# Pg15_FPGA_5CGX.net
KiCad netlist of a schematic drawn in Altium Designer
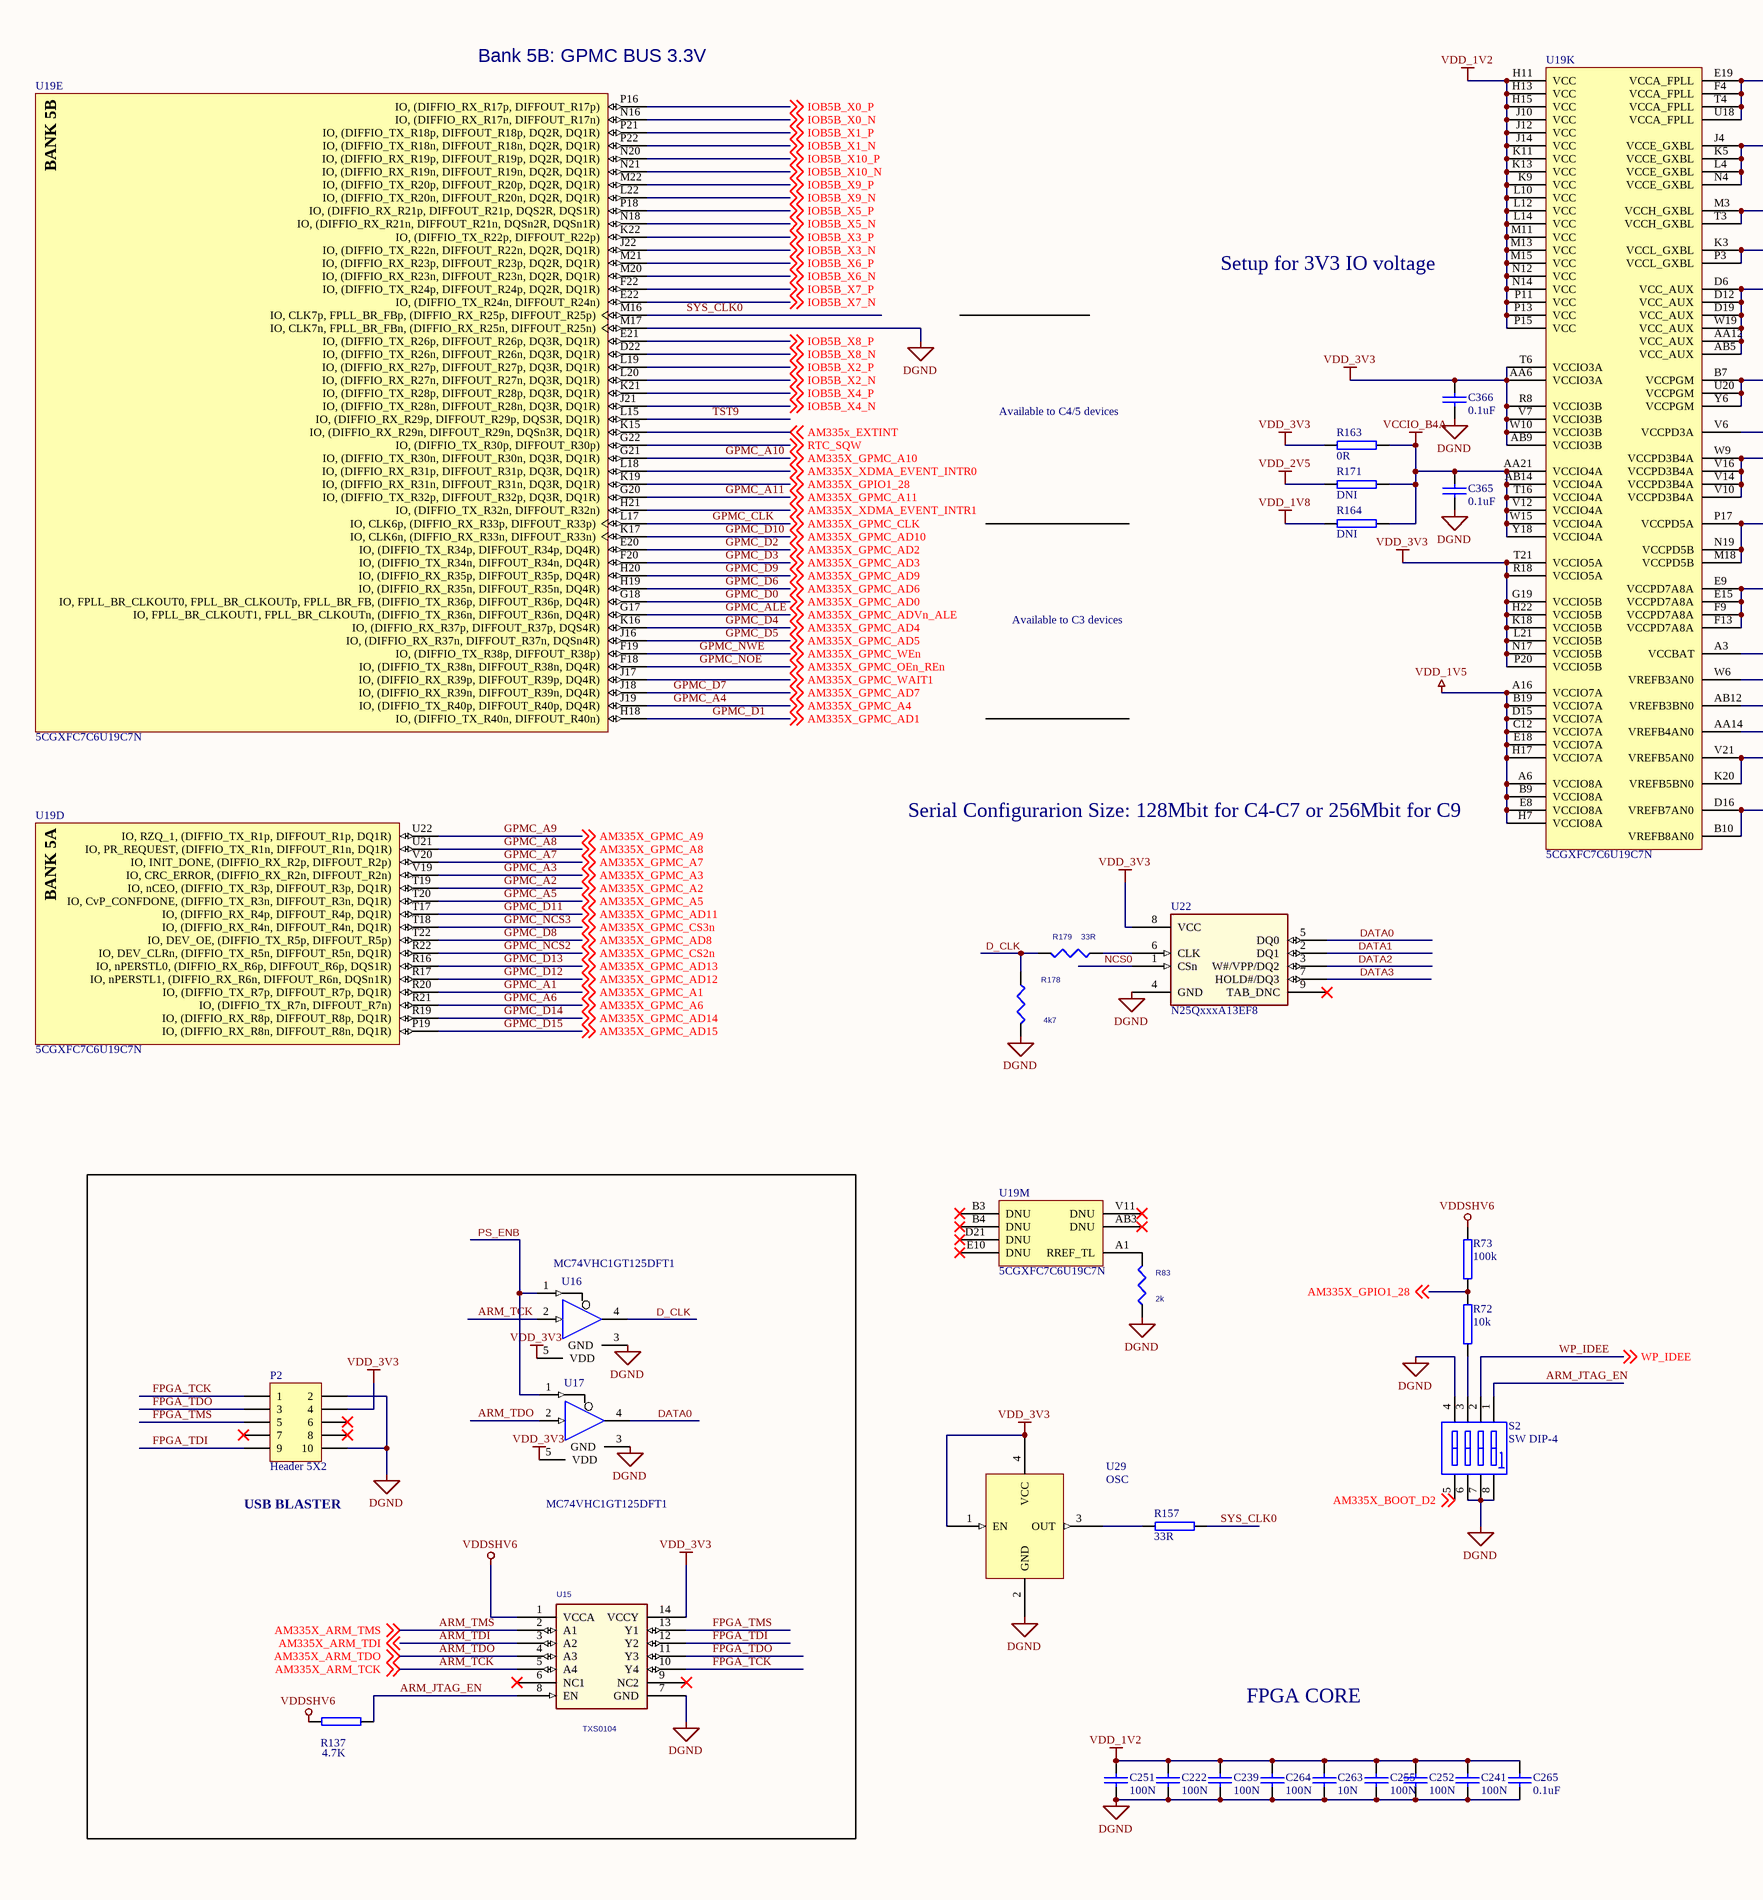
[diagram p0: Pg15_FPGA_5CGX.SchDoc, left]
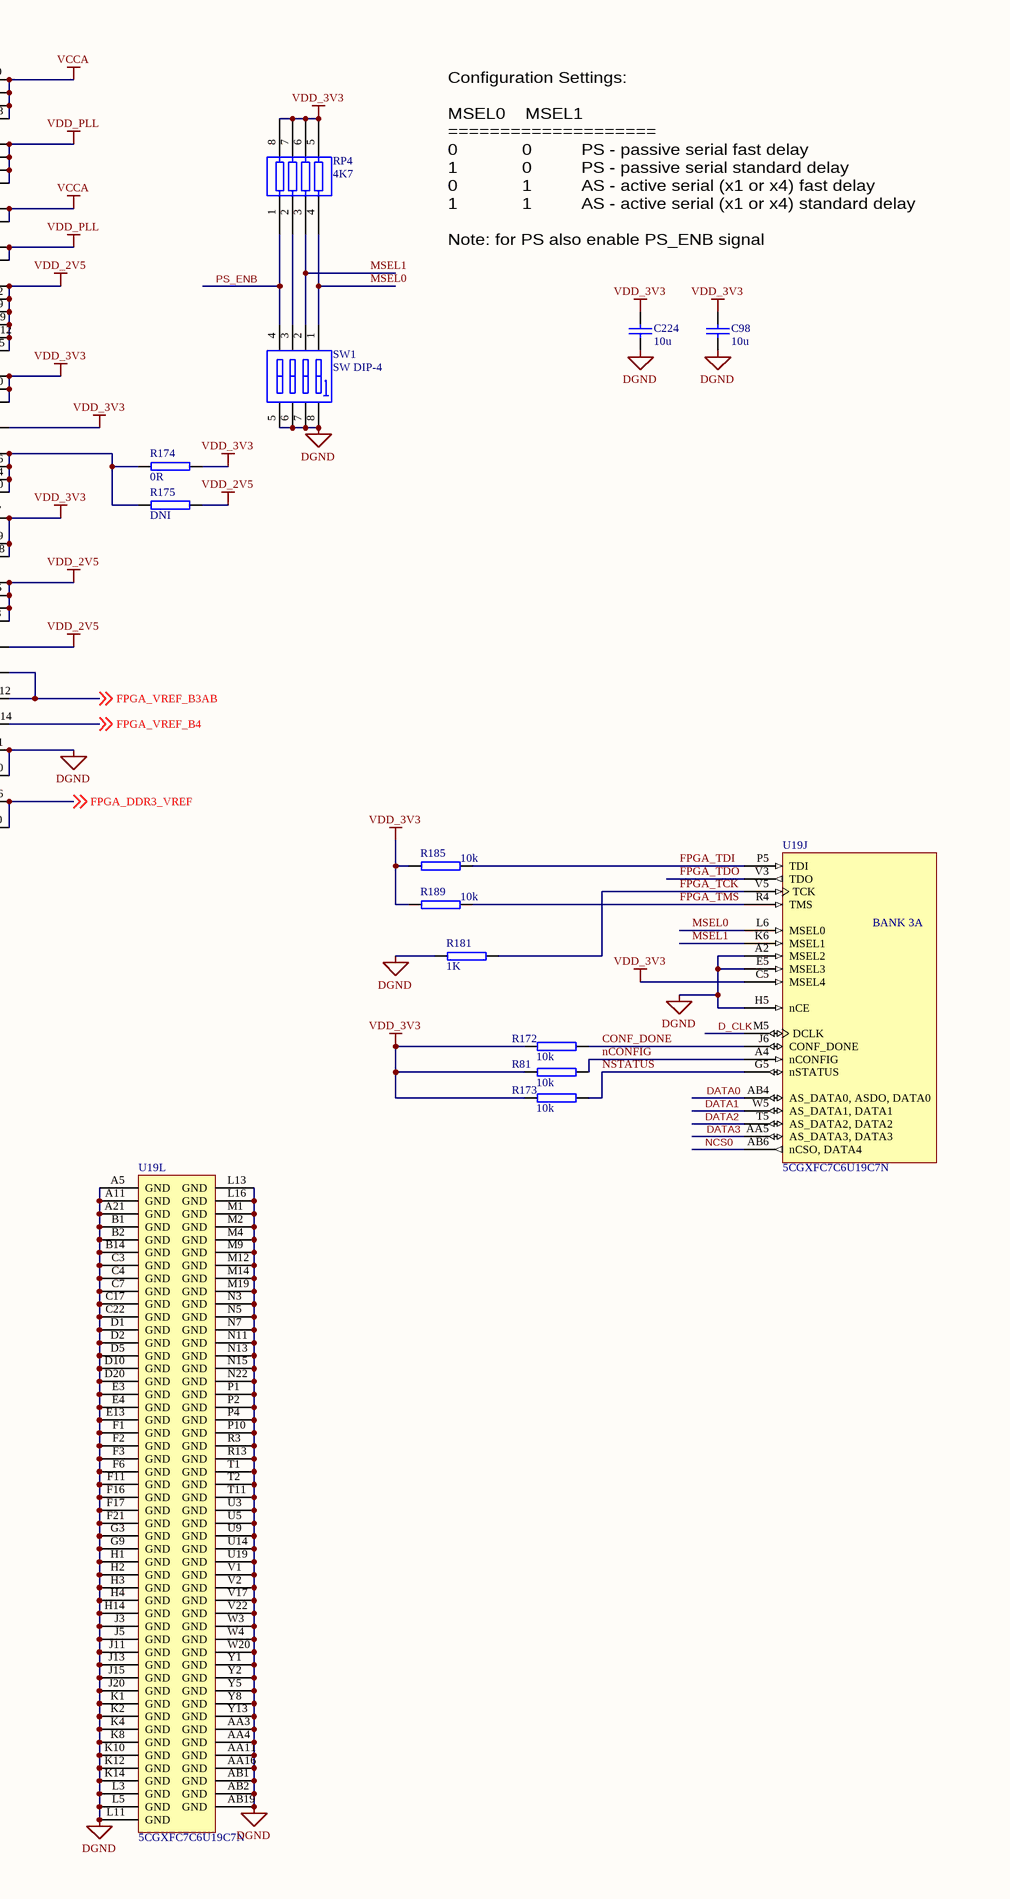
[diagram p1: Pg15_FPGA_5CGX.SchDoc, right]

(export (version "E")
  (design (tool "Eeschema 10.0.6"))
  (components
    (comp (ref "C98")
      (value "10u")
      (footprint "0603")
      (description "NON-POLARISED CAP")
      (libsource (lib "Fireflash_B") (part "CAP"))
    )
    (comp (ref "C222")
      (value "100N")
      (footprint "0603")
      (description "NON-POLARISED CAP")
      (libsource (lib "Fireflash_B") (part "CAP"))
    )
    (comp (ref "C224")
      (value "10u")
      (footprint "0603")
      (description "NON-POLARISED CAP")
      (libsource (lib "Fireflash_B") (part "CAP"))
    )
    (comp (ref "C239")
      (value "100N")
      (footprint "sc0402")
      (description "NON-POLARISED CAP")
      (libsource (lib "Fireflash_B") (part "CAP"))
    )
    (comp (ref "C241")
      (value "100N")
      (footprint "sc0402")
      (description "NON-POLARISED CAP")
      (libsource (lib "Fireflash_B") (part "CAP"))
    )
    (comp (ref "C251")
      (value "100N")
      (footprint "sc0402")
      (description "NON-POLARISED CAP")
      (libsource (lib "Fireflash_B") (part "CAP"))
    )
    (comp (ref "C252")
      (value "100N")
      (footprint "sc0402")
      (description "NON-POLARISED CAP")
      (libsource (lib "Fireflash_B") (part "CAP"))
    )
    (comp (ref "C255")
      (value "100N")
      (footprint "sc0402")
      (description "NON-POLARISED CAP")
      (libsource (lib "Fireflash_B") (part "CAP"))
    )
    (comp (ref "C263")
      (value "10N")
      (footprint "sc0402")
      (description "NON-POLARISED CAP")
      (libsource (lib "Fireflash_B") (part "CAP"))
    )
    (comp (ref "C264")
      (value "100N")
      (footprint "sc0402")
      (description "NON-POLARISED CAP")
      (libsource (lib "Fireflash_B") (part "CAP"))
    )
    (comp (ref "C265")
      (value "0.1uF")
      (footprint "sc0402")
      (description "NON-POLARISED CAP")
      (libsource (lib "Fireflash_B") (part "CAP"))
    )
    (comp (ref "C365")
      (value "0.1uF")
      (footprint "sc0402")
      (description "NON-POLARISED CAP")
      (libsource (lib "Fireflash_B") (part "CAP"))
    )
    (comp (ref "C366")
      (value "0.1uF")
      (footprint "sc0402")
      (description "NON-POLARISED CAP")
      (libsource (lib "Fireflash_B") (part "CAP"))
    )
    (comp (ref "P2")
      (value "Header 5X2")
      (footprint "HDR2X5")
      (description "Header, 5-Pin, Dual row")
      (fields (field (name "PUBLISHER") "Altium Limited"))
      (libsource (lib "Miscellaneous Connectors") (part "Header 5X2"))
    )
    (comp (ref "R72")
      (value "10k")
      (footprint "sc0402")
      (description "Resistor")
      (libsource (lib "Ibis4") (part "RES"))
    )
    (comp (ref "R73")
      (value "100k")
      (footprint "sc0402")
      (description "Resistor")
      (libsource (lib "Ibis4") (part "RES"))
    )
    (comp (ref "R81")
      (value "10k")
      (footprint "sc0402")
      (description "Resistor")
      (libsource (lib "Ibis4") (part "RES"))
    )
    (comp (ref "R83")
      (value "2k")
      (footprint "SM-7351-RES-0402")
      (description "Resistor 10Kohm 1/16W 5% 0402")
      (fields (field (name "MFR") "Rohm") (field (name "TIINTPARTNUMBER") "1R0168"))
      (libsource (lib "*") (part "10KOhmResistor1/16W0402"))
    )
    (comp (ref "R137")
      (value "4.7K")
      (footprint "sc0402")
      (description "RESISTOR")
      (libsource (lib "Fireflash_B") (part "RES"))
    )
    (comp (ref "R157")
      (value "33R")
      (footprint "sc0402")
      (description "Resistor")
      (libsource (lib "Ibis4") (part "RES"))
    )
    (comp (ref "R163")
      (value "0R")
      (footprint "sc0402")
      (description "Resistor")
      (libsource (lib "Ibis4") (part "RES"))
    )
    (comp (ref "R164")
      (value "DNI")
      (footprint "sc0402")
      (description "Resistor")
      (libsource (lib "Ibis4") (part "RES"))
    )
    (comp (ref "R171")
      (value "DNI")
      (footprint "sc0402")
      (description "Resistor")
      (libsource (lib "Ibis4") (part "RES"))
    )
    (comp (ref "R172")
      (value "10k")
      (footprint "sc0402")
      (description "Resistor")
      (libsource (lib "Ibis4") (part "RES"))
    )
    (comp (ref "R173")
      (value "10k")
      (footprint "sc0402")
      (description "Resistor")
      (libsource (lib "Ibis4") (part "RES"))
    )
    (comp (ref "R174")
      (value "0R")
      (footprint "sc0402")
      (description "Resistor")
      (libsource (lib "Ibis4") (part "RES"))
    )
    (comp (ref "R175")
      (value "DNI")
      (footprint "sc0402")
      (description "Resistor")
      (libsource (lib "Ibis4") (part "RES"))
    )
    (comp (ref "R178")
      (value "4k7")
      (footprint "SM-7351-RES-0402")
      (description "Resistor 10Kohm 1/16W 5% 0402")
      (fields (field (name "MFR") "Rohm") (field (name "TIINTPARTNUMBER") "1R0168"))
      (libsource (lib "*") (part "10KOhmResistor1/16W0402"))
    )
    (comp (ref "R179")
      (value "33R")
      (footprint "SM-7351-RES-0402")
      (description "Resistor 10Kohm 1/16W 5% 0402")
      (fields (field (name "MFR") "Rohm") (field (name "TIINTPARTNUMBER") "1R0168"))
      (libsource (lib "*") (part "10KOhmResistor1/16W0402"))
    )
    (comp (ref "R181")
      (value "1K")
      (footprint "sc0402")
      (description "Resistor")
      (libsource (lib "Ibis4") (part "RES"))
    )
    (comp (ref "R185")
      (value "10k")
      (footprint "sc0402")
      (description "Resistor")
      (libsource (lib "Ibis4") (part "RES"))
    )
    (comp (ref "R189")
      (value "10k")
      (footprint "sc0402")
      (description "Resistor")
      (libsource (lib "Ibis4") (part "RES"))
    )
    (comp (ref "RP4")
      (value "4K7")
      (footprint "1206X4")
      (description "QUAD DIP RESISTOR PACK")
      (libsource (lib "*") (part "RESDIP4"))
    )
    (comp (ref "S2")
      (value "SW DIP-4")
      (footprint "PcbLib1:DIPSOP8")
      (description "DIP Switch, 4 Position, SPST")
      (fields (field (name "PUBLISHER") "Altium Limited"))
      (libsource (lib "ARMflash1a") (part "SW DIP-4"))
    )
    (comp (ref "SW1")
      (value "SW DIP-4")
      (footprint "DIPSOP8")
      (description "DIP Switch, 4 Position, SPST")
      (fields (field (name "PUBLISHER") "Altium Limited"))
      (libsource (lib "ARMflashC3_revb") (part "SW DIP-4"))
    )
    (comp (ref "U15")
      (value "TXS0104")
      (footprint "RU-14")
      (description "IC - LOW VOLTAGE 1.2 V TO 5.5 V, 4 CHANNEL, BIDIRECTIONAL, LOGIC LEVEL TRANSLATOR, 14-TSSOP")
      (fields
        (field (name "MANUFACTURER PART NUM") "ADG3304BRUZ")
        (field (name "MANUFACTURER") "Analog Devices")
      )
      (libsource (lib "ARMflash_mini") (part "ADG3304"))
    )
    (comp (ref "U16")
      (value "MC74VHC1GT125DFT1")
      (footprint "419A-01_N")
      (description "Non-Inverting Buffer / CMOS Logic Level Shifter with LSTTL-Compatible Inputs")
      (fields (field (name "PUBLISHER") "Altium Limited"))
      (libsource (lib "ON Semi Logic Buffer Line Driver") (part "MC74VHC1GT125DFT1"))
    )
    (comp (ref "U17")
      (value "MC74VHC1GT125DFT1")
      (footprint "419A-01_N")
      (description "Non-Inverting Buffer / CMOS Logic Level Shifter with LSTTL-Compatible Inputs")
      (fields (field (name "PUBLISHER") "Altium Limited"))
      (libsource (lib "ON Semi Logic Buffer Line Driver") (part "MC74VHC1GT125DFT1"))
    )
    (comp (ref "U19")
      (value "5CGXFC7C6U19C7N")
      (footprint "ALTR-UBGA484_A-190")
      (fields (field (name "MANUFACTURER") "Altera"))
      (libsource (lib "Altera Cyclone V") (part "5CGXFC7C6U19C7N"))
    )
    (comp (ref "U22")
      (value "N25QxxxA13EF8")
      (footprint "QFN127P600X500X85_HS-9N")
      (libsource (lib "C5_SOC_DEVKIT_C_162_Library") (part "N25QxxxA13EF8"))
    )
    (comp (ref "U29")
      (value "OSC")
      (footprint "Osc 3.2x2.5")
      (description "XTAL OSCILLATOR MODULE")
      (libsource (lib "Fireflash_B") (part "OSC"))
    )
  )
  (nets
    (net (code "1") (name "/ARM_JTAG_EN") (class "Default")
      (node (ref "R137") (pin "1") (pintype "passive"))
      (node (ref "S2") (pin "1") (pinfunction "A1_1") (pintype "passive"))
      (node (ref "U15") (pin "8") (pinfunction "EN_8") (pintype "input"))
    )
    (net (code "2") (name "/CONF_DONE") (class "Default")
      (node (ref "R172") (pin "1") (pintype "passive"))
      (node (ref "U19") (pin "J6") (pinfunction "CONF_DONE_J6") (pintype "bidirectional"))
    )
    (net (code "3") (name "/DATA0") (class "Default")
      (node (ref "U17") (pin "4") (pinfunction "Y_4") (pintype "tri_state"))
      (node (ref "U19") (pin "AB4") (pinfunction "AS_DATA0,_ASDO,_DATA0_AB4") (pintype "bidirectional"))
      (node (ref "U22") (pin "5") (pinfunction "DQ0_5") (pintype "bidirectional"))
    )
    (net (code "4") (name "/DATA1") (class "Default")
      (node (ref "U19") (pin "W5") (pinfunction "AS_DATA1,_DATA1_W5") (pintype "bidirectional"))
      (node (ref "U22") (pin "2") (pinfunction "DQ1_2") (pintype "bidirectional"))
    )
    (net (code "5") (name "/DATA2") (class "Default")
      (node (ref "U19") (pin "T5") (pinfunction "AS_DATA2,_DATA2_T5") (pintype "bidirectional"))
      (node (ref "U22") (pin "3") (pinfunction "W#/VPP/DQ2_3") (pintype "bidirectional"))
    )
    (net (code "6") (name "/DATA3") (class "Default")
      (node (ref "U19") (pin "AA5") (pinfunction "AS_DATA3,_DATA3_AA5") (pintype "bidirectional"))
      (node (ref "U22") (pin "7") (pinfunction "HOLD#/DQ3_7") (pintype "bidirectional"))
    )
    (net (code "7") (name "/D_CLK") (class "Default")
      (node (ref "R178") (pin "2") (pinfunction "P2_2") (pintype "passive"))
      (node (ref "R179") (pin "1") (pinfunction "P1_1") (pintype "passive"))
      (node (ref "U16") (pin "4") (pinfunction "Y_4") (pintype "tri_state"))
      (node (ref "U19") (pin "M5") (pinfunction "DCLK_M5") (pintype "bidirectional"))
    )
    (net (code "8") (name "/FPGA_TCK") (class "Default")
      (node (ref "P2") (pin "1") (pinfunction "1_1") (pintype "passive"))
      (node (ref "R181") (pin "1") (pintype "passive"))
      (node (ref "U15") (pin "10") (pinfunction "Y4_10") (pintype "bidirectional"))
      (node (ref "U19") (pin "V5") (pinfunction "TCK_V5") (pintype "input"))
    )
    (net (code "9") (name "/FPGA_TDI") (class "Default")
      (node (ref "P2") (pin "9") (pinfunction "9_9") (pintype "passive"))
      (node (ref "R185") (pin "1") (pintype "passive"))
      (node (ref "U15") (pin "12") (pinfunction "Y2_12") (pintype "bidirectional"))
      (node (ref "U19") (pin "P5") (pinfunction "TDI_P5") (pintype "input"))
    )
    (net (code "10") (name "/FPGA_TDO") (class "Default")
      (node (ref "P2") (pin "3") (pinfunction "3_3") (pintype "passive"))
      (node (ref "U15") (pin "11") (pinfunction "Y3_11") (pintype "bidirectional"))
      (node (ref "U19") (pin "V3") (pinfunction "TDO_V3") (pintype "output"))
    )
    (net (code "11") (name "/FPGA_TMS") (class "Default")
      (node (ref "P2") (pin "5") (pinfunction "5_5") (pintype "passive"))
      (node (ref "R189") (pin "1") (pintype "passive"))
      (node (ref "U15") (pin "13") (pinfunction "Y1_13") (pintype "bidirectional"))
      (node (ref "U19") (pin "R4") (pinfunction "TMS_R4") (pintype "input"))
    )
    (net (code "12") (name "/MSEL0") (class "Default")
      (node (ref "RP4") (pin "4") (pintype "passive"))
      (node (ref "SW1") (pin "1") (pinfunction "A1_1") (pintype "passive"))
      (node (ref "U19") (pin "L6") (pinfunction "MSEL0_L6") (pintype "input"))
    )
    (net (code "13") (name "/MSEL1") (class "Default")
      (node (ref "RP4") (pin "3") (pintype "passive"))
      (node (ref "SW1") (pin "2") (pinfunction "A2_2") (pintype "passive"))
      (node (ref "U19") (pin "K6") (pinfunction "MSEL1_K6") (pintype "input"))
    )
    (net (code "14") (name "/NCS0") (class "Default")
      (node (ref "U19") (pin "AB6") (pinfunction "nCSO,_DATA4_AB6") (pintype "output"))
      (node (ref "U22") (pin "1") (pinfunction "CSn_1") (pintype "input"))
    )
    (net (code "15") (name "/NSTATUS") (class "Default")
      (node (ref "R173") (pin "1") (pintype "passive"))
      (node (ref "U19") (pin "G5") (pinfunction "nSTATUS_G5") (pintype "bidirectional"))
    )
    (net (code "16") (name "/PS_ENB") (class "Default")
      (node (ref "RP4") (pin "1") (pintype "passive"))
      (node (ref "SW1") (pin "4") (pinfunction "A4_4") (pintype "passive"))
      (node (ref "U16") (pin "1") (pinfunction "~{OE}_1") (pintype "input"))
      (node (ref "U17") (pin "1") (pinfunction "~{OE}_1") (pintype "input"))
    )
    (net (code "17") (name "/SYS_CLK0") (class "Default")
      (node (ref "R157") (pin "2") (pintype "passive"))
      (node (ref "U19") (pin "M16") (pinfunction "IO,_CLK7p,_FPLL_BR_FBp,_(DIFFIO_RX_R25p,_DIFFOUT_R25p)_M16") (pintype "bidirectional"))
    )
    (net (code "18") (name "/TST9") (class "Default")
      (node (ref "U19") (pin "L15") (pinfunction "IO,_(DIFFIO_RX_R29p,_DIFFOUT_R29p,_DQS3R,_DQ1R)_L15") (pintype "bidirectional"))
    )
    (net (code "19") (name "/nCONFIG") (class "Default")
      (node (ref "R81") (pin "1") (pintype "passive"))
      (node (ref "U19") (pin "A4") (pinfunction "nCONFIG_A4") (pintype "input"))
    )
    (net (code "20") (name "AM335X_ARM_TCK") (class "Default")
      (node (ref "U15") (pin "5") (pinfunction "A4_5") (pintype "bidirectional"))
      (node (ref "U16") (pin "2") (pinfunction "A_2") (pintype "input"))
    )
    (net (code "21") (name "AM335X_ARM_TDI") (class "Default")
      (node (ref "U15") (pin "3") (pinfunction "A2_3") (pintype "bidirectional"))
    )
    (net (code "22") (name "AM335X_ARM_TDO") (class "Default")
      (node (ref "U15") (pin "4") (pinfunction "A3_4") (pintype "bidirectional"))
      (node (ref "U17") (pin "2") (pinfunction "A_2") (pintype "input"))
    )
    (net (code "23") (name "AM335X_ARM_TMS") (class "Default")
      (node (ref "U15") (pin "2") (pinfunction "A1_2") (pintype "bidirectional"))
    )
    (net (code "24") (name "AM335X_BOOT_D2") (class "Default")
      (node (ref "S2") (pin "5") (pinfunction "B4_5") (pintype "passive"))
    )
    (net (code "25") (name "AM335X_GPIO1_28") (class "Default")
      (node (ref "R72") (pin "2") (pintype "passive"))
      (node (ref "R73") (pin "1") (pintype "passive"))
      (node (ref "U19") (pin "K19") (pinfunction "IO,_(DIFFIO_RX_R31n,_DIFFOUT_R31n,_DQ3R,_DQ1R)_K19") (pintype "bidirectional"))
    )
    (net (code "26") (name "AM335X_GPMC_A1") (class "Default")
      (node (ref "U19") (pin "R20") (pinfunction "IO,_(DIFFIO_TX_R7p,_DIFFOUT_R7p,_DQ1R)_R20") (pintype "bidirectional"))
    )
    (net (code "27") (name "AM335X_GPMC_A2") (class "Default")
      (node (ref "U19") (pin "T19") (pinfunction "IO,_nCEO,_(DIFFIO_TX_R3p,_DIFFOUT_R3p,_DQ1R)_T19") (pintype "bidirectional"))
    )
    (net (code "28") (name "AM335X_GPMC_A3") (class "Default")
      (node (ref "U19") (pin "V19") (pinfunction "IO,_CRC_ERROR,_(DIFFIO_RX_R2n,_DIFFOUT_R2n)_V19") (pintype "bidirectional"))
    )
    (net (code "29") (name "AM335X_GPMC_A4") (class "Default")
      (node (ref "U19") (pin "J19") (pinfunction "IO,_(DIFFIO_TX_R40p,_DIFFOUT_R40p,_DQ4R)_J19") (pintype "bidirectional"))
    )
    (net (code "30") (name "AM335X_GPMC_A5") (class "Default")
      (node (ref "U19") (pin "T20") (pinfunction "IO,_CvP_CONFDONE,_(DIFFIO_TX_R3n,_DIFFOUT_R3n,_DQ1R)_T20") (pintype "bidirectional"))
    )
    (net (code "31") (name "AM335X_GPMC_A6") (class "Default")
      (node (ref "U19") (pin "R21") (pinfunction "IO,_(DIFFIO_TX_R7n,_DIFFOUT_R7n)_R21") (pintype "bidirectional"))
    )
    (net (code "32") (name "AM335X_GPMC_A7") (class "Default")
      (node (ref "U19") (pin "V20") (pinfunction "IO,_INIT_DONE,_(DIFFIO_RX_R2p,_DIFFOUT_R2p)_V20") (pintype "bidirectional"))
    )
    (net (code "33") (name "AM335X_GPMC_A8") (class "Default")
      (node (ref "U19") (pin "U21") (pinfunction "IO,_PR_REQUEST,_(DIFFIO_TX_R1n,_DIFFOUT_R1n,_DQ1R)_U21") (pintype "bidirectional"))
    )
    (net (code "34") (name "AM335X_GPMC_A9") (class "Default")
      (node (ref "U19") (pin "U22") (pinfunction "IO,_RZQ_1,_(DIFFIO_TX_R1p,_DIFFOUT_R1p,_DQ1R)_U22") (pintype "bidirectional"))
    )
    (net (code "35") (name "AM335X_GPMC_A10") (class "Default")
      (node (ref "U19") (pin "G21") (pinfunction "IO,_(DIFFIO_TX_R30n,_DIFFOUT_R30n,_DQ3R,_DQ1R)_G21") (pintype "bidirectional"))
    )
    (net (code "36") (name "AM335X_GPMC_A11") (class "Default")
      (node (ref "U19") (pin "G20") (pinfunction "IO,_(DIFFIO_TX_R32p,_DIFFOUT_R32p,_DQ3R,_DQ1R)_G20") (pintype "bidirectional"))
    )
    (net (code "37") (name "AM335X_GPMC_AD0") (class "Default")
      (node (ref "U19") (pin "G18") (pinfunction "IO,_FPLL_BR_CLKOUT0,_FPLL_BR_CLKOUTp,_FPLL_BR_FB,_(DIFFIO_TX_R36p,_DIFFOUT_R36p,_DQ4R)_G18") (pintype "bidirectional"))
    )
    (net (code "38") (name "AM335X_GPMC_AD1") (class "Default")
      (node (ref "U19") (pin "H18") (pinfunction "IO,_(DIFFIO_TX_R40n,_DIFFOUT_R40n)_H18") (pintype "bidirectional"))
    )
    (net (code "39") (name "AM335X_GPMC_AD2") (class "Default")
      (node (ref "U19") (pin "E20") (pinfunction "IO,_(DIFFIO_TX_R34p,_DIFFOUT_R34p,_DQ4R)_E20") (pintype "bidirectional"))
    )
    (net (code "40") (name "AM335X_GPMC_AD3") (class "Default")
      (node (ref "U19") (pin "F20") (pinfunction "IO,_(DIFFIO_TX_R34n,_DIFFOUT_R34n,_DQ4R)_F20") (pintype "bidirectional"))
    )
    (net (code "41") (name "AM335X_GPMC_AD4") (class "Default")
      (node (ref "U19") (pin "K16") (pinfunction "IO,_(DIFFIO_RX_R37p,_DIFFOUT_R37p,_DQS4R)_K16") (pintype "bidirectional"))
    )
    (net (code "42") (name "AM335X_GPMC_AD5") (class "Default")
      (node (ref "U19") (pin "J16") (pinfunction "IO,_(DIFFIO_RX_R37n,_DIFFOUT_R37n,_DQSn4R)_J16") (pintype "bidirectional"))
    )
    (net (code "43") (name "AM335X_GPMC_AD6") (class "Default")
      (node (ref "U19") (pin "H19") (pinfunction "IO,_(DIFFIO_RX_R35n,_DIFFOUT_R35n,_DQ4R)_H19") (pintype "bidirectional"))
    )
    (net (code "44") (name "AM335X_GPMC_AD7") (class "Default")
      (node (ref "U19") (pin "J18") (pinfunction "IO,_(DIFFIO_RX_R39n,_DIFFOUT_R39n,_DQ4R)_J18") (pintype "bidirectional"))
    )
    (net (code "45") (name "AM335X_GPMC_AD8") (class "Default")
      (node (ref "U19") (pin "T22") (pinfunction "IO,_DEV_OE,_(DIFFIO_TX_R5p,_DIFFOUT_R5p)_T22") (pintype "bidirectional"))
    )
    (net (code "46") (name "AM335X_GPMC_AD9") (class "Default")
      (node (ref "U19") (pin "H20") (pinfunction "IO,_(DIFFIO_RX_R35p,_DIFFOUT_R35p,_DQ4R)_H20") (pintype "bidirectional"))
    )
    (net (code "47") (name "AM335X_GPMC_AD10") (class "Default")
      (node (ref "U19") (pin "K17") (pinfunction "IO,_CLK6n,_(DIFFIO_RX_R33n,_DIFFOUT_R33n)_K17") (pintype "bidirectional"))
    )
    (net (code "48") (name "AM335X_GPMC_AD11") (class "Default")
      (node (ref "U19") (pin "T17") (pinfunction "IO,_(DIFFIO_RX_R4p,_DIFFOUT_R4p,_DQ1R)_T17") (pintype "bidirectional"))
    )
    (net (code "49") (name "AM335X_GPMC_AD12") (class "Default")
      (node (ref "U19") (pin "R17") (pinfunction "IO,_nPERSTL1,_(DIFFIO_RX_R6n,_DIFFOUT_R6n,_DQSn1R)_R17") (pintype "bidirectional"))
    )
    (net (code "50") (name "AM335X_GPMC_AD13") (class "Default")
      (node (ref "U19") (pin "R16") (pinfunction "IO,_nPERSTL0,_(DIFFIO_RX_R6p,_DIFFOUT_R6p,_DQS1R)_R16") (pintype "bidirectional"))
    )
    (net (code "51") (name "AM335X_GPMC_AD14") (class "Default")
      (node (ref "U19") (pin "R19") (pinfunction "IO,_(DIFFIO_RX_R8p,_DIFFOUT_R8p,_DQ1R)_R19") (pintype "bidirectional"))
    )
    (net (code "52") (name "AM335X_GPMC_AD15") (class "Default")
      (node (ref "U19") (pin "P19") (pinfunction "IO,_(DIFFIO_RX_R8n,_DIFFOUT_R8n,_DQ1R)_P19") (pintype "bidirectional"))
    )
    (net (code "53") (name "AM335X_GPMC_ADVn_ALE") (class "Default")
      (node (ref "U19") (pin "G17") (pinfunction "IO,_FPLL_BR_CLKOUT1,_FPLL_BR_CLKOUTn,_(DIFFIO_TX_R36n,_DIFFOUT_R36n,_DQ4R)_G17") (pintype "bidirectional"))
    )
    (net (code "54") (name "AM335X_GPMC_CLK") (class "Default")
      (node (ref "U19") (pin "L17") (pinfunction "IO,_CLK6p,_(DIFFIO_RX_R33p,_DIFFOUT_R33p)_L17") (pintype "bidirectional"))
    )
    (net (code "55") (name "AM335X_GPMC_CS2n") (class "Default")
      (node (ref "U19") (pin "R22") (pinfunction "IO,_DEV_CLRn,_(DIFFIO_TX_R5n,_DIFFOUT_R5n,_DQ1R)_R22") (pintype "bidirectional"))
    )
    (net (code "56") (name "AM335X_GPMC_CS3n") (class "Default")
      (node (ref "U19") (pin "T18") (pinfunction "IO,_(DIFFIO_RX_R4n,_DIFFOUT_R4n,_DQ1R)_T18") (pintype "bidirectional"))
    )
    (net (code "57") (name "AM335X_GPMC_OEn_REn") (class "Default")
      (node (ref "U19") (pin "F18") (pinfunction "IO,_(DIFFIO_TX_R38n,_DIFFOUT_R38n,_DQ4R)_F18") (pintype "bidirectional"))
    )
    (net (code "58") (name "AM335X_GPMC_WAIT1") (class "Default")
      (node (ref "U19") (pin "J17") (pinfunction "IO,_(DIFFIO_RX_R39p,_DIFFOUT_R39p,_DQ4R)_J17") (pintype "bidirectional"))
    )
    (net (code "59") (name "AM335X_GPMC_WEn") (class "Default")
      (node (ref "U19") (pin "F19") (pinfunction "IO,_(DIFFIO_TX_R38p,_DIFFOUT_R38p)_F19") (pintype "bidirectional"))
    )
    (net (code "60") (name "AM335X_XDMA_EVENT_INTR0") (class "Default")
      (node (ref "U19") (pin "L18") (pinfunction "IO,_(DIFFIO_RX_R31p,_DIFFOUT_R31p,_DQ3R,_DQ1R)_L18") (pintype "bidirectional"))
    )
    (net (code "61") (name "AM335X_XDMA_EVENT_INTR1") (class "Default")
      (node (ref "U19") (pin "H21") (pinfunction "IO,_(DIFFIO_TX_R32n,_DIFFOUT_R32n)_H21") (pintype "bidirectional"))
    )
    (net (code "62") (name "AM335x_EXTINT") (class "Default")
      (node (ref "U19") (pin "K15") (pinfunction "IO,_(DIFFIO_RX_R29n,_DIFFOUT_R29n,_DQSn3R,_DQ1R)_K15") (pintype "bidirectional"))
    )
    (net (code "63") (name "DGND") (class "Default")
      (node (ref "C222") (pin "2") (pintype "passive"))
      (node (ref "C224") (pin "2") (pintype "passive"))
      (node (ref "C239") (pin "2") (pintype "passive"))
      (node (ref "C241") (pin "2") (pintype "passive"))
      (node (ref "C251") (pin "2") (pintype "passive"))
      (node (ref "C252") (pin "2") (pintype "passive"))
      (node (ref "C255") (pin "2") (pintype "passive"))
      (node (ref "C263") (pin "2") (pintype "passive"))
      (node (ref "C264") (pin "2") (pintype "passive"))
      (node (ref "C265") (pin "2") (pintype "passive"))
      (node (ref "C365") (pin "2") (pintype "passive"))
      (node (ref "C366") (pin "2") (pintype "passive"))
      (node (ref "C98") (pin "2") (pintype "passive"))
      (node (ref "P2") (pin "10") (pinfunction "10_10") (pintype "passive"))
      (node (ref "P2") (pin "2") (pinfunction "2_2") (pintype "passive"))
      (node (ref "R178") (pin "1") (pinfunction "P1_1") (pintype "passive"))
      (node (ref "R181") (pin "2") (pintype "passive"))
      (node (ref "R83") (pin "2") (pinfunction "P2_2") (pintype "passive"))
      (node (ref "S2") (pin "4") (pinfunction "A4_4") (pintype "passive"))
      (node (ref "S2") (pin "6") (pinfunction "B3_6") (pintype "passive"))
      (node (ref "S2") (pin "7") (pinfunction "B2_7") (pintype "passive"))
      (node (ref "S2") (pin "8") (pinfunction "B1_8") (pintype "passive"))
      (node (ref "SW1") (pin "5") (pinfunction "B4_5") (pintype "passive"))
      (node (ref "SW1") (pin "6") (pinfunction "B3_6") (pintype "passive"))
      (node (ref "SW1") (pin "7") (pinfunction "B2_7") (pintype "passive"))
      (node (ref "SW1") (pin "8") (pinfunction "B1_8") (pintype "passive"))
      (node (ref "U15") (pin "7") (pinfunction "GND_7") (pintype "power_in"))
      (node (ref "U16") (pin "3") (pinfunction "GND_3") (pintype "power_in"))
      (node (ref "U17") (pin "3") (pinfunction "GND_3") (pintype "power_in"))
      (node (ref "U19") (pin "A11") (pinfunction "GND_A11") (pintype "power_in"))
      (node (ref "U19") (pin "A2") (pinfunction "MSEL2_A2") (pintype "input"))
      (node (ref "U19") (pin "A21") (pinfunction "GND_A21") (pintype "power_in"))
      (node (ref "U19") (pin "A5") (pinfunction "GND_A5") (pintype "power_in"))
      (node (ref "U19") (pin "AA11") (pinfunction "GND_AA11") (pintype "power_in"))
      (node (ref "U19") (pin "AA16") (pinfunction "GND_AA16") (pintype "power_in"))
      (node (ref "U19") (pin "AA3") (pinfunction "GND_AA3") (pintype "power_in"))
      (node (ref "U19") (pin "AA4") (pinfunction "GND_AA4") (pintype "power_in"))
      (node (ref "U19") (pin "AB1") (pinfunction "GND_AB1") (pintype "power_in"))
      (node (ref "U19") (pin "AB19") (pinfunction "GND_AB19") (pintype "power_in"))
      (node (ref "U19") (pin "AB2") (pinfunction "GND_AB2") (pintype "power_in"))
      (node (ref "U19") (pin "B1") (pinfunction "GND_B1") (pintype "power_in"))
      (node (ref "U19") (pin "B14") (pinfunction "GND_B14") (pintype "power_in"))
      (node (ref "U19") (pin "B2") (pinfunction "GND_B2") (pintype "power_in"))
      (node (ref "U19") (pin "C17") (pinfunction "GND_C17") (pintype "power_in"))
      (node (ref "U19") (pin "C22") (pinfunction "GND_C22") (pintype "power_in"))
      (node (ref "U19") (pin "C3") (pinfunction "GND_C3") (pintype "power_in"))
      (node (ref "U19") (pin "C4") (pinfunction "GND_C4") (pintype "power_in"))
      (node (ref "U19") (pin "C7") (pinfunction "GND_C7") (pintype "power_in"))
      (node (ref "U19") (pin "D1") (pinfunction "GND_D1") (pintype "power_in"))
      (node (ref "U19") (pin "D10") (pinfunction "GND_D10") (pintype "power_in"))
      (node (ref "U19") (pin "D2") (pinfunction "GND_D2") (pintype "power_in"))
      (node (ref "U19") (pin "D20") (pinfunction "GND_D20") (pintype "power_in"))
      (node (ref "U19") (pin "D5") (pinfunction "GND_D5") (pintype "power_in"))
      (node (ref "U19") (pin "E13") (pinfunction "GND_E13") (pintype "power_in"))
      (node (ref "U19") (pin "E3") (pinfunction "GND_E3") (pintype "power_in"))
      (node (ref "U19") (pin "E4") (pinfunction "GND_E4") (pintype "power_in"))
      (node (ref "U19") (pin "E5") (pinfunction "MSEL3_E5") (pintype "input"))
      (node (ref "U19") (pin "F1") (pinfunction "GND_F1") (pintype "power_in"))
      (node (ref "U19") (pin "F11") (pinfunction "GND_F11") (pintype "power_in"))
      (node (ref "U19") (pin "F16") (pinfunction "GND_F16") (pintype "power_in"))
      (node (ref "U19") (pin "F17") (pinfunction "GND_F17") (pintype "power_in"))
      (node (ref "U19") (pin "F2") (pinfunction "GND_F2") (pintype "power_in"))
      (node (ref "U19") (pin "F21") (pinfunction "GND_F21") (pintype "power_in"))
      (node (ref "U19") (pin "F3") (pinfunction "GND_F3") (pintype "power_in"))
      (node (ref "U19") (pin "F6") (pinfunction "GND_F6") (pintype "power_in"))
      (node (ref "U19") (pin "G3") (pinfunction "GND_G3") (pintype "power_in"))
      (node (ref "U19") (pin "G9") (pinfunction "GND_G9") (pintype "power_in"))
      (node (ref "U19") (pin "H1") (pinfunction "GND_H1") (pintype "power_in"))
      (node (ref "U19") (pin "H14") (pinfunction "GND_H14") (pintype "power_in"))
      (node (ref "U19") (pin "H2") (pinfunction "GND_H2") (pintype "power_in"))
      (node (ref "U19") (pin "H3") (pinfunction "GND_H3") (pintype "power_in"))
      (node (ref "U19") (pin "H4") (pinfunction "GND_H4") (pintype "power_in"))
      (node (ref "U19") (pin "H5") (pinfunction "nCE_H5") (pintype "input"))
      (node (ref "U19") (pin "J11") (pinfunction "GND_J11") (pintype "power_in"))
      (node (ref "U19") (pin "J13") (pinfunction "GND_J13") (pintype "power_in"))
      (node (ref "U19") (pin "J15") (pinfunction "GND_J15") (pintype "power_in"))
      (node (ref "U19") (pin "J20") (pinfunction "GND_J20") (pintype "power_in"))
      (node (ref "U19") (pin "J3") (pinfunction "GND_J3") (pintype "power_in"))
      (node (ref "U19") (pin "J5") (pinfunction "GND_J5") (pintype "power_in"))
      (node (ref "U19") (pin "K1") (pinfunction "GND_K1") (pintype "power_in"))
      (node (ref "U19") (pin "K10") (pinfunction "GND_K10") (pintype "power_in"))
      (node (ref "U19") (pin "K12") (pinfunction "GND_K12") (pintype "power_in"))
      (node (ref "U19") (pin "K14") (pinfunction "GND_K14") (pintype "power_in"))
      (node (ref "U19") (pin "K2") (pinfunction "GND_K2") (pintype "power_in"))
      (node (ref "U19") (pin "K20") (pinfunction "VREFB5BN0_K20") (pintype "power_in"))
      (node (ref "U19") (pin "K4") (pinfunction "GND_K4") (pintype "power_in"))
      (node (ref "U19") (pin "K8") (pinfunction "GND_K8") (pintype "power_in"))
      (node (ref "U19") (pin "L11") (pinfunction "GND_L11") (pintype "power_in"))
      (node (ref "U19") (pin "L13") (pinfunction "GND_L13") (pintype "power_in"))
      (node (ref "U19") (pin "L16") (pinfunction "GND_L16") (pintype "power_in"))
      (node (ref "U19") (pin "L3") (pinfunction "GND_L3") (pintype "power_in"))
      (node (ref "U19") (pin "L5") (pinfunction "GND_L5") (pintype "power_in"))
      (node (ref "U19") (pin "M1") (pinfunction "GND_M1") (pintype "power_in"))
      (node (ref "U19") (pin "M12") (pinfunction "GND_M12") (pintype "power_in"))
      (node (ref "U19") (pin "M14") (pinfunction "GND_M14") (pintype "power_in"))
      (node (ref "U19") (pin "M17") (pinfunction "IO,_CLK7n,_FPLL_BR_FBn,_(DIFFIO_RX_R25n,_DIFFOUT_R25n)_M17") (pintype "bidirectional"))
      (node (ref "U19") (pin "M19") (pinfunction "GND_M19") (pintype "power_in"))
      (node (ref "U19") (pin "M2") (pinfunction "GND_M2") (pintype "power_in"))
      (node (ref "U19") (pin "M4") (pinfunction "GND_M4") (pintype "power_in"))
      (node (ref "U19") (pin "M9") (pinfunction "GND_M9") (pintype "power_in"))
      (node (ref "U19") (pin "N11") (pinfunction "GND_N11") (pintype "power_in"))
      (node (ref "U19") (pin "N13") (pinfunction "GND_N13") (pintype "power_in"))
      (node (ref "U19") (pin "N15") (pinfunction "GND_N15") (pintype "power_in"))
      (node (ref "U19") (pin "N22") (pinfunction "GND_N22") (pintype "power_in"))
      (node (ref "U19") (pin "N3") (pinfunction "GND_N3") (pintype "power_in"))
      (node (ref "U19") (pin "N5") (pinfunction "GND_N5") (pintype "power_in"))
      (node (ref "U19") (pin "N7") (pinfunction "GND_N7") (pintype "power_in"))
      (node (ref "U19") (pin "P1") (pinfunction "GND_P1") (pintype "power_in"))
      (node (ref "U19") (pin "P10") (pinfunction "GND_P10") (pintype "power_in"))
      (node (ref "U19") (pin "P2") (pinfunction "GND_P2") (pintype "power_in"))
      (node (ref "U19") (pin "P4") (pinfunction "GND_P4") (pintype "power_in"))
      (node (ref "U19") (pin "R13") (pinfunction "GND_R13") (pintype "power_in"))
      (node (ref "U19") (pin "R3") (pinfunction "GND_R3") (pintype "power_in"))
      (node (ref "U19") (pin "T1") (pinfunction "GND_T1") (pintype "power_in"))
      (node (ref "U19") (pin "T11") (pinfunction "GND_T11") (pintype "power_in"))
      (node (ref "U19") (pin "T2") (pinfunction "GND_T2") (pintype "power_in"))
      (node (ref "U19") (pin "U14") (pinfunction "GND_U14") (pintype "power_in"))
      (node (ref "U19") (pin "U19") (pinfunction "GND_U19") (pintype "power_in"))
      (node (ref "U19") (pin "U3") (pinfunction "GND_U3") (pintype "power_in"))
      (node (ref "U19") (pin "U5") (pinfunction "GND_U5") (pintype "power_in"))
      (node (ref "U19") (pin "U9") (pinfunction "GND_U9") (pintype "power_in"))
      (node (ref "U19") (pin "V1") (pinfunction "GND_V1") (pintype "power_in"))
      (node (ref "U19") (pin "V17") (pinfunction "GND_V17") (pintype "power_in"))
      (node (ref "U19") (pin "V2") (pinfunction "GND_V2") (pintype "power_in"))
      (node (ref "U19") (pin "V21") (pinfunction "VREFB5AN0_V21") (pintype "power_in"))
      (node (ref "U19") (pin "V22") (pinfunction "GND_V22") (pintype "power_in"))
      (node (ref "U19") (pin "W20") (pinfunction "GND_W20") (pintype "power_in"))
      (node (ref "U19") (pin "W3") (pinfunction "GND_W3") (pintype "power_in"))
      (node (ref "U19") (pin "W4") (pinfunction "GND_W4") (pintype "power_in"))
      (node (ref "U19") (pin "Y1") (pinfunction "GND_Y1") (pintype "power_in"))
      (node (ref "U19") (pin "Y13") (pinfunction "GND_Y13") (pintype "power_in"))
      (node (ref "U19") (pin "Y2") (pinfunction "GND_Y2") (pintype "power_in"))
      (node (ref "U19") (pin "Y5") (pinfunction "GND_Y5") (pintype "power_in"))
      (node (ref "U19") (pin "Y8") (pinfunction "GND_Y8") (pintype "power_in"))
      (node (ref "U22") (pin "4") (pinfunction "GND_4") (pintype "power_in"))
      (node (ref "U29") (pin "2") (pinfunction "GND_2") (pintype "power_in"))
    )
    (net (code "64") (name "FPGA_DDR3_VREF") (class "Default")
      (node (ref "U19") (pin "B10") (pinfunction "VREFB8AN0_B10") (pintype "power_in"))
      (node (ref "U19") (pin "D16") (pinfunction "VREFB7AN0_D16") (pintype "power_in"))
    )
    (net (code "65") (name "FPGA_VREF_B3AB") (class "Default")
      (node (ref "U19") (pin "AB12") (pinfunction "VREFB3BN0_AB12") (pintype "power_in"))
      (node (ref "U19") (pin "W6") (pinfunction "VREFB3AN0_W6") (pintype "power_in"))
    )
    (net (code "66") (name "FPGA_VREF_B4") (class "Default")
      (node (ref "U19") (pin "AA14") (pinfunction "VREFB4AN0_AA14") (pintype "power_in"))
    )
    (net (code "67") (name "IOB5B_X0_N") (class "Default")
      (node (ref "U19") (pin "N16") (pinfunction "IO,_(DIFFIO_RX_R17n,_DIFFOUT_R17n)_N16") (pintype "bidirectional"))
    )
    (net (code "68") (name "IOB5B_X0_P") (class "Default")
      (node (ref "U19") (pin "P16") (pinfunction "IO,_(DIFFIO_RX_R17p,_DIFFOUT_R17p)_P16") (pintype "bidirectional"))
    )
    (net (code "69") (name "IOB5B_X1_N") (class "Default")
      (node (ref "U19") (pin "P22") (pinfunction "IO,_(DIFFIO_TX_R18n,_DIFFOUT_R18n,_DQ2R,_DQ1R)_P22") (pintype "bidirectional"))
    )
    (net (code "70") (name "IOB5B_X1_P") (class "Default")
      (node (ref "U19") (pin "P21") (pinfunction "IO,_(DIFFIO_TX_R18p,_DIFFOUT_R18p,_DQ2R,_DQ1R)_P21") (pintype "bidirectional"))
    )
    (net (code "71") (name "IOB5B_X2_N") (class "Default")
      (node (ref "U19") (pin "L20") (pinfunction "IO,_(DIFFIO_RX_R27n,_DIFFOUT_R27n,_DQ3R,_DQ1R)_L20") (pintype "bidirectional"))
    )
    (net (code "72") (name "IOB5B_X2_P") (class "Default")
      (node (ref "U19") (pin "L19") (pinfunction "IO,_(DIFFIO_RX_R27p,_DIFFOUT_R27p,_DQ3R,_DQ1R)_L19") (pintype "bidirectional"))
    )
    (net (code "73") (name "IOB5B_X3_N") (class "Default")
      (node (ref "U19") (pin "J22") (pinfunction "IO,_(DIFFIO_TX_R22n,_DIFFOUT_R22n,_DQ2R,_DQ1R)_J22") (pintype "bidirectional"))
    )
    (net (code "74") (name "IOB5B_X3_P") (class "Default")
      (node (ref "U19") (pin "K22") (pinfunction "IO,_(DIFFIO_TX_R22p,_DIFFOUT_R22p)_K22") (pintype "bidirectional"))
    )
    (net (code "75") (name "IOB5B_X4_N") (class "Default")
      (node (ref "U19") (pin "J21") (pinfunction "IO,_(DIFFIO_TX_R28n,_DIFFOUT_R28n,_DQ3R,_DQ1R)_J21") (pintype "bidirectional"))
    )
    (net (code "76") (name "IOB5B_X4_P") (class "Default")
      (node (ref "U19") (pin "K21") (pinfunction "IO,_(DIFFIO_TX_R28p,_DIFFOUT_R28p,_DQ3R,_DQ1R)_K21") (pintype "bidirectional"))
    )
    (net (code "77") (name "IOB5B_X5_N") (class "Default")
      (node (ref "U19") (pin "N18") (pinfunction "IO,_(DIFFIO_RX_R21n,_DIFFOUT_R21n,_DQSn2R,_DQSn1R)_N18") (pintype "bidirectional"))
    )
    (net (code "78") (name "IOB5B_X5_P") (class "Default")
      (node (ref "U19") (pin "P18") (pinfunction "IO,_(DIFFIO_RX_R21p,_DIFFOUT_R21p,_DQS2R,_DQS1R)_P18") (pintype "bidirectional"))
    )
    (net (code "79") (name "IOB5B_X6_N") (class "Default")
      (node (ref "U19") (pin "M20") (pinfunction "IO,_(DIFFIO_RX_R23n,_DIFFOUT_R23n,_DQ2R,_DQ1R)_M20") (pintype "bidirectional"))
    )
    (net (code "80") (name "IOB5B_X6_P") (class "Default")
      (node (ref "U19") (pin "M21") (pinfunction "IO,_(DIFFIO_RX_R23p,_DIFFOUT_R23p,_DQ2R,_DQ1R)_M21") (pintype "bidirectional"))
    )
    (net (code "81") (name "IOB5B_X7_N") (class "Default")
      (node (ref "U19") (pin "E22") (pinfunction "IO,_(DIFFIO_TX_R24n,_DIFFOUT_R24n)_E22") (pintype "bidirectional"))
    )
    (net (code "82") (name "IOB5B_X7_P") (class "Default")
      (node (ref "U19") (pin "F22") (pinfunction "IO,_(DIFFIO_TX_R24p,_DIFFOUT_R24p,_DQ2R,_DQ1R)_F22") (pintype "bidirectional"))
    )
    (net (code "83") (name "IOB5B_X8_N") (class "Default")
      (node (ref "U19") (pin "D22") (pinfunction "IO,_(DIFFIO_TX_R26n,_DIFFOUT_R26n,_DQ3R,_DQ1R)_D22") (pintype "bidirectional"))
    )
    (net (code "84") (name "IOB5B_X8_P") (class "Default")
      (node (ref "U19") (pin "E21") (pinfunction "IO,_(DIFFIO_TX_R26p,_DIFFOUT_R26p,_DQ3R,_DQ1R)_E21") (pintype "bidirectional"))
    )
    (net (code "85") (name "IOB5B_X9_N") (class "Default")
      (node (ref "U19") (pin "L22") (pinfunction "IO,_(DIFFIO_TX_R20n,_DIFFOUT_R20n,_DQ2R,_DQ1R)_L22") (pintype "bidirectional"))
    )
    (net (code "86") (name "IOB5B_X9_P") (class "Default")
      (node (ref "U19") (pin "M22") (pinfunction "IO,_(DIFFIO_TX_R20p,_DIFFOUT_R20p,_DQ2R,_DQ1R)_M22") (pintype "bidirectional"))
    )
    (net (code "87") (name "IOB5B_X10_N") (class "Default")
      (node (ref "U19") (pin "N21") (pinfunction "IO,_(DIFFIO_RX_R19n,_DIFFOUT_R19n,_DQ2R,_DQ1R)_N21") (pintype "bidirectional"))
    )
    (net (code "88") (name "IOB5B_X10_P") (class "Default")
      (node (ref "U19") (pin "N20") (pinfunction "IO,_(DIFFIO_RX_R19p,_DIFFOUT_R19p,_DQ2R,_DQ1R)_N20") (pintype "bidirectional"))
    )
    (net (code "89") (name "Net-(R83-P1)") (class "Default")
      (node (ref "R83") (pin "1") (pinfunction "P1_1") (pintype "passive"))
      (node (ref "U19") (pin "A1") (pinfunction "RREF_TL_A1") (pintype "passive"))
    )
    (net (code "90") (name "Net-(R174-Pad2)") (class "Default")
      (node (ref "R174") (pin "2") (pintype "passive"))
      (node (ref "R175") (pin "2") (pintype "passive"))
      (node (ref "U19") (pin "V10") (pinfunction "VCCPD3B4A_V10") (pintype "power_in"))
      (node (ref "U19") (pin "V14") (pinfunction "VCCPD3B4A_V14") (pintype "power_in"))
      (node (ref "U19") (pin "V16") (pinfunction "VCCPD3B4A_V16") (pintype "power_in"))
      (node (ref "U19") (pin "W9") (pinfunction "VCCPD3B4A_W9") (pintype "power_in"))
    )
    (net (code "91") (name "Net-(R179-P2)") (class "Default")
      (node (ref "R179") (pin "2") (pinfunction "P2_2") (pintype "passive"))
      (node (ref "U22") (pin "6") (pinfunction "CLK_6") (pintype "input"))
    )
    (net (code "92") (name "Net-(S2-A3)") (class "Default")
      (node (ref "R72") (pin "1") (pintype "passive"))
      (node (ref "S2") (pin "3") (pinfunction "A3_3") (pintype "passive"))
    )
    (net (code "93") (name "Net-(SW1-A3)") (class "Default")
      (node (ref "RP4") (pin "2") (pintype "passive"))
      (node (ref "SW1") (pin "3") (pinfunction "A3_3") (pintype "passive"))
    )
    (net (code "94") (name "Net-(U29-OUT)") (class "Default")
      (node (ref "R157") (pin "1") (pintype "passive"))
      (node (ref "U29") (pin "3") (pinfunction "OUT_3") (pintype "output"))
    )
    (net (code "95") (name "RTC_SQW") (class "Default")
      (node (ref "U19") (pin "G22") (pinfunction "IO,_(DIFFIO_TX_R30p,_DIFFOUT_R30p)_G22") (pintype "bidirectional"))
    )
    (net (code "96") (name "VCCA") (class "Default")
      (node (ref "U19") (pin "E19") (pinfunction "VCCA_FPLL_E19") (pintype "power_in"))
      (node (ref "U19") (pin "F4") (pinfunction "VCCA_FPLL_F4") (pintype "power_in"))
      (node (ref "U19") (pin "M3") (pinfunction "VCCH_GXBL_M3") (pintype "power_in"))
      (node (ref "U19") (pin "T3") (pinfunction "VCCH_GXBL_T3") (pintype "power_in"))
      (node (ref "U19") (pin "T4") (pinfunction "VCCA_FPLL_T4") (pintype "power_in"))
      (node (ref "U19") (pin "U18") (pinfunction "VCCA_FPLL_U18") (pintype "power_in"))
    )
    (net (code "97") (name "VCCIO_B4A") (class "Default")
      (node (ref "C365") (pin "1") (pintype "passive"))
      (node (ref "R163") (pin "1") (pintype "passive"))
      (node (ref "R164") (pin "1") (pintype "passive"))
      (node (ref "R171") (pin "1") (pintype "passive"))
      (node (ref "U19") (pin "AA21") (pinfunction "VCCIO4A_AA21") (pintype "power_in"))
      (node (ref "U19") (pin "AB14") (pinfunction "VCCIO4A_AB14") (pintype "power_in"))
      (node (ref "U19") (pin "T16") (pinfunction "VCCIO4A_T16") (pintype "power_in"))
      (node (ref "U19") (pin "V12") (pinfunction "VCCIO4A_V12") (pintype "power_in"))
      (node (ref "U19") (pin "W15") (pinfunction "VCCIO4A_W15") (pintype "power_in"))
      (node (ref "U19") (pin "Y18") (pinfunction "VCCIO4A_Y18") (pintype "power_in"))
    )
    (net (code "98") (name "VDDSHV6") (class "Default")
      (node (ref "R137") (pin "2") (pintype "passive"))
      (node (ref "R73") (pin "2") (pintype "passive"))
      (node (ref "U15") (pin "1") (pinfunction "VCCA_1") (pintype "power_in"))
    )
    (net (code "99") (name "VDD_1V2") (class "Default")
      (node (ref "C222") (pin "1") (pintype "passive"))
      (node (ref "C239") (pin "1") (pintype "passive"))
      (node (ref "C241") (pin "1") (pintype "passive"))
      (node (ref "C251") (pin "1") (pintype "passive"))
      (node (ref "C252") (pin "1") (pintype "passive"))
      (node (ref "C255") (pin "1") (pintype "passive"))
      (node (ref "C263") (pin "1") (pintype "passive"))
      (node (ref "C264") (pin "1") (pintype "passive"))
      (node (ref "C265") (pin "1") (pintype "passive"))
      (node (ref "U19") (pin "H11") (pinfunction "VCC_H11") (pintype "power_in"))
      (node (ref "U19") (pin "H13") (pinfunction "VCC_H13") (pintype "power_in"))
      (node (ref "U19") (pin "H15") (pinfunction "VCC_H15") (pintype "power_in"))
      (node (ref "U19") (pin "J10") (pinfunction "VCC_J10") (pintype "power_in"))
      (node (ref "U19") (pin "J12") (pinfunction "VCC_J12") (pintype "power_in"))
      (node (ref "U19") (pin "J14") (pinfunction "VCC_J14") (pintype "power_in"))
      (node (ref "U19") (pin "K11") (pinfunction "VCC_K11") (pintype "power_in"))
      (node (ref "U19") (pin "K13") (pinfunction "VCC_K13") (pintype "power_in"))
      (node (ref "U19") (pin "K9") (pinfunction "VCC_K9") (pintype "power_in"))
      (node (ref "U19") (pin "L10") (pinfunction "VCC_L10") (pintype "power_in"))
      (node (ref "U19") (pin "L12") (pinfunction "VCC_L12") (pintype "power_in"))
      (node (ref "U19") (pin "L14") (pinfunction "VCC_L14") (pintype "power_in"))
      (node (ref "U19") (pin "M11") (pinfunction "VCC_M11") (pintype "power_in"))
      (node (ref "U19") (pin "M13") (pinfunction "VCC_M13") (pintype "power_in"))
      (node (ref "U19") (pin "M15") (pinfunction "VCC_M15") (pintype "power_in"))
      (node (ref "U19") (pin "N12") (pinfunction "VCC_N12") (pintype "power_in"))
      (node (ref "U19") (pin "N14") (pinfunction "VCC_N14") (pintype "power_in"))
      (node (ref "U19") (pin "P11") (pinfunction "VCC_P11") (pintype "power_in"))
      (node (ref "U19") (pin "P13") (pinfunction "VCC_P13") (pintype "power_in"))
      (node (ref "U19") (pin "P15") (pinfunction "VCC_P15") (pintype "power_in"))
    )
    (net (code "100") (name "VDD_1V5") (class "Default")
      (node (ref "U19") (pin "A16") (pinfunction "VCCIO7A_A16") (pintype "power_in"))
      (node (ref "U19") (pin "A6") (pinfunction "VCCIO8A_A6") (pintype "power_in"))
      (node (ref "U19") (pin "B19") (pinfunction "VCCIO7A_B19") (pintype "power_in"))
      (node (ref "U19") (pin "B9") (pinfunction "VCCIO8A_B9") (pintype "power_in"))
      (node (ref "U19") (pin "C12") (pinfunction "VCCIO7A_C12") (pintype "power_in"))
      (node (ref "U19") (pin "D15") (pinfunction "VCCIO7A_D15") (pintype "power_in"))
      (node (ref "U19") (pin "E18") (pinfunction "VCCIO7A_E18") (pintype "power_in"))
      (node (ref "U19") (pin "E8") (pinfunction "VCCIO8A_E8") (pintype "power_in"))
      (node (ref "U19") (pin "H17") (pinfunction "VCCIO7A_H17") (pintype "power_in"))
      (node (ref "U19") (pin "H7") (pinfunction "VCCIO8A_H7") (pintype "power_in"))
    )
    (net (code "101") (name "VDD_1V8") (class "Default") (node (ref "R164") (pin "2") (pintype "passive")))
    (net (code "102") (name "VDD_2V5") (class "Default")
      (node (ref "R171") (pin "2") (pintype "passive"))
      (node (ref "R175") (pin "1") (pintype "passive"))
      (node (ref "U19") (pin "A3") (pinfunction "VCCBAT_A3") (pintype "power_in"))
      (node (ref "U19") (pin "AA12") (pinfunction "VCC_AUX_AA12") (pintype "power_in"))
      (node (ref "U19") (pin "AB5") (pinfunction "VCC_AUX_AB5") (pintype "power_in"))
      (node (ref "U19") (pin "D12") (pinfunction "VCC_AUX_D12") (pintype "power_in"))
      (node (ref "U19") (pin "D19") (pinfunction "VCC_AUX_D19") (pintype "power_in"))
      (node (ref "U19") (pin "D6") (pinfunction "VCC_AUX_D6") (pintype "power_in"))
      (node (ref "U19") (pin "E15") (pinfunction "VCCPD7A8A_E15") (pintype "power_in"))
      (node (ref "U19") (pin "E9") (pinfunction "VCCPD7A8A_E9") (pintype "power_in"))
      (node (ref "U19") (pin "F13") (pinfunction "VCCPD7A8A_F13") (pintype "power_in"))
      (node (ref "U19") (pin "F9") (pinfunction "VCCPD7A8A_F9") (pintype "power_in"))
      (node (ref "U19") (pin "W19") (pinfunction "VCC_AUX_W19") (pintype "power_in"))
    )
    (net (code "103") (name "VDD_3V3") (class "Default")
      (node (ref "C224") (pin "1") (pintype "passive"))
      (node (ref "C366") (pin "1") (pintype "passive"))
      (node (ref "C98") (pin "1") (pintype "passive"))
      (node (ref "P2") (pin "4") (pinfunction "4_4") (pintype "passive"))
      (node (ref "R163") (pin "2") (pintype "passive"))
      (node (ref "R172") (pin "2") (pintype "passive"))
      (node (ref "R173") (pin "2") (pintype "passive"))
      (node (ref "R174") (pin "1") (pintype "passive"))
      (node (ref "R185") (pin "2") (pintype "passive"))
      (node (ref "R189") (pin "2") (pintype "passive"))
      (node (ref "R81") (pin "2") (pintype "passive"))
      (node (ref "RP4") (pin "5") (pintype "passive"))
      (node (ref "RP4") (pin "6") (pintype "passive"))
      (node (ref "RP4") (pin "7") (pintype "passive"))
      (node (ref "RP4") (pin "8") (pintype "passive"))
      (node (ref "U15") (pin "14") (pinfunction "VCCY_14") (pintype "power_in"))
      (node (ref "U16") (pin "5") (pinfunction "VDD_5") (pintype "power_in"))
      (node (ref "U17") (pin "5") (pinfunction "VDD_5") (pintype "power_in"))
      (node (ref "U19") (pin "AA6") (pinfunction "VCCIO3A_AA6") (pintype "power_in"))
      (node (ref "U19") (pin "AB9") (pinfunction "VCCIO3B_AB9") (pintype "power_in"))
      (node (ref "U19") (pin "B7") (pinfunction "VCCPGM_B7") (pintype "power_in"))
      (node (ref "U19") (pin "C5") (pinfunction "MSEL4_C5") (pintype "input"))
      (node (ref "U19") (pin "G19") (pinfunction "VCCIO5B_G19") (pintype "power_in"))
      (node (ref "U19") (pin "H22") (pinfunction "VCCIO5B_H22") (pintype "power_in"))
      (node (ref "U19") (pin "K18") (pinfunction "VCCIO5B_K18") (pintype "power_in"))
      (node (ref "U19") (pin "L21") (pinfunction "VCCIO5B_L21") (pintype "power_in"))
      (node (ref "U19") (pin "M18") (pinfunction "VCCPD5B_M18") (pintype "power_in"))
      (node (ref "U19") (pin "N17") (pinfunction "VCCIO5B_N17") (pintype "power_in"))
      (node (ref "U19") (pin "N19") (pinfunction "VCCPD5B_N19") (pintype "power_in"))
      (node (ref "U19") (pin "P17") (pinfunction "VCCPD5A_P17") (pintype "power_in"))
      (node (ref "U19") (pin "P20") (pinfunction "VCCIO5B_P20") (pintype "power_in"))
      (node (ref "U19") (pin "R18") (pinfunction "VCCIO5A_R18") (pintype "power_in"))
      (node (ref "U19") (pin "R8") (pinfunction "VCCIO3B_R8") (pintype "power_in"))
      (node (ref "U19") (pin "T21") (pinfunction "VCCIO5A_T21") (pintype "power_in"))
      (node (ref "U19") (pin "T6") (pinfunction "VCCIO3A_T6") (pintype "power_in"))
      (node (ref "U19") (pin "U20") (pinfunction "VCCPGM_U20") (pintype "power_in"))
      (node (ref "U19") (pin "V6") (pinfunction "VCCPD3A_V6") (pintype "power_in"))
      (node (ref "U19") (pin "V7") (pinfunction "VCCIO3B_V7") (pintype "power_in"))
      (node (ref "U19") (pin "W10") (pinfunction "VCCIO3B_W10") (pintype "power_in"))
      (node (ref "U19") (pin "Y6") (pinfunction "VCCPGM_Y6") (pintype "power_in"))
      (node (ref "U22") (pin "8") (pinfunction "VCC_8") (pintype "power_in"))
      (node (ref "U29") (pin "1") (pinfunction "EN_1") (pintype "input"))
      (node (ref "U29") (pin "4") (pinfunction "VCC_4") (pintype "power_in"))
    )
    (net (code "104") (name "VDD_PLL") (class "Default")
      (node (ref "U19") (pin "J4") (pinfunction "VCCE_GXBL_J4") (pintype "power_in"))
      (node (ref "U19") (pin "K3") (pinfunction "VCCL_GXBL_K3") (pintype "power_in"))
      (node (ref "U19") (pin "K5") (pinfunction "VCCE_GXBL_K5") (pintype "power_in"))
      (node (ref "U19") (pin "L4") (pinfunction "VCCE_GXBL_L4") (pintype "power_in"))
      (node (ref "U19") (pin "N4") (pinfunction "VCCE_GXBL_N4") (pintype "power_in"))
      (node (ref "U19") (pin "P3") (pinfunction "VCCL_GXBL_P3") (pintype "power_in"))
    )
    (net (code "105") (name "WP_IDEE") (class "Default")
      (node (ref "S2") (pin "2") (pinfunction "A2_2") (pintype "passive"))
    )
    (net (code "106") (name "unconnected-(P2-Pad6)") (class "Default")
      (node (ref "P2") (pin "6") (pinfunction "6_6") (pintype "passive+no_connect"))
    )
    (net (code "107") (name "unconnected-(P2-Pad7)") (class "Default")
      (node (ref "P2") (pin "7") (pinfunction "7_7") (pintype "passive+no_connect"))
    )
    (net (code "108") (name "unconnected-(P2-Pad8)") (class "Default")
      (node (ref "P2") (pin "8") (pinfunction "8_8") (pintype "passive+no_connect"))
    )
    (net (code "109") (name "unconnected-(U15-NC1-Pad6)") (class "Default")
      (node (ref "U15") (pin "6") (pinfunction "NC1_6") (pintype "passive+no_connect"))
    )
    (net (code "110") (name "unconnected-(U15-NC2-Pad9)") (class "Default")
      (node (ref "U15") (pin "9") (pinfunction "NC2_9") (pintype "passive+no_connect"))
    )
    (net (code "111") (name "unconnected-(U19M-DNU-PadAB3)") (class "Default")
      (node (ref "U19") (pin "AB3") (pinfunction "DNU_AB3") (pintype "passive+no_connect"))
    )
    (net (code "112") (name "unconnected-(U19M-DNU-PadB3)") (class "Default")
      (node (ref "U19") (pin "B3") (pinfunction "DNU_B3") (pintype "passive+no_connect"))
    )
    (net (code "113") (name "unconnected-(U19M-DNU-PadB4)") (class "Default")
      (node (ref "U19") (pin "B4") (pinfunction "DNU_B4") (pintype "passive+no_connect"))
    )
    (net (code "114") (name "unconnected-(U19M-DNU-PadD21)") (class "Default")
      (node (ref "U19") (pin "D21") (pinfunction "DNU_D21") (pintype "passive+no_connect"))
    )
    (net (code "115") (name "unconnected-(U19M-DNU-PadE10)") (class "Default")
      (node (ref "U19") (pin "E10") (pinfunction "DNU_E10") (pintype "passive+no_connect"))
    )
    (net (code "116") (name "unconnected-(U19M-DNU-PadV11)") (class "Default")
      (node (ref "U19") (pin "V11") (pinfunction "DNU_V11") (pintype "passive+no_connect"))
    )
    (net (code "117") (name "unconnected-(U22-TAB_DNC-Pad9)") (class "Default")
      (node (ref "U22") (pin "9") (pinfunction "TAB_DNC_9") (pintype "passive+no_connect"))
    )
  )
)
